# Module_B_High-Speed.net
KiCad netlist of a schematic drawn in Altium Designer
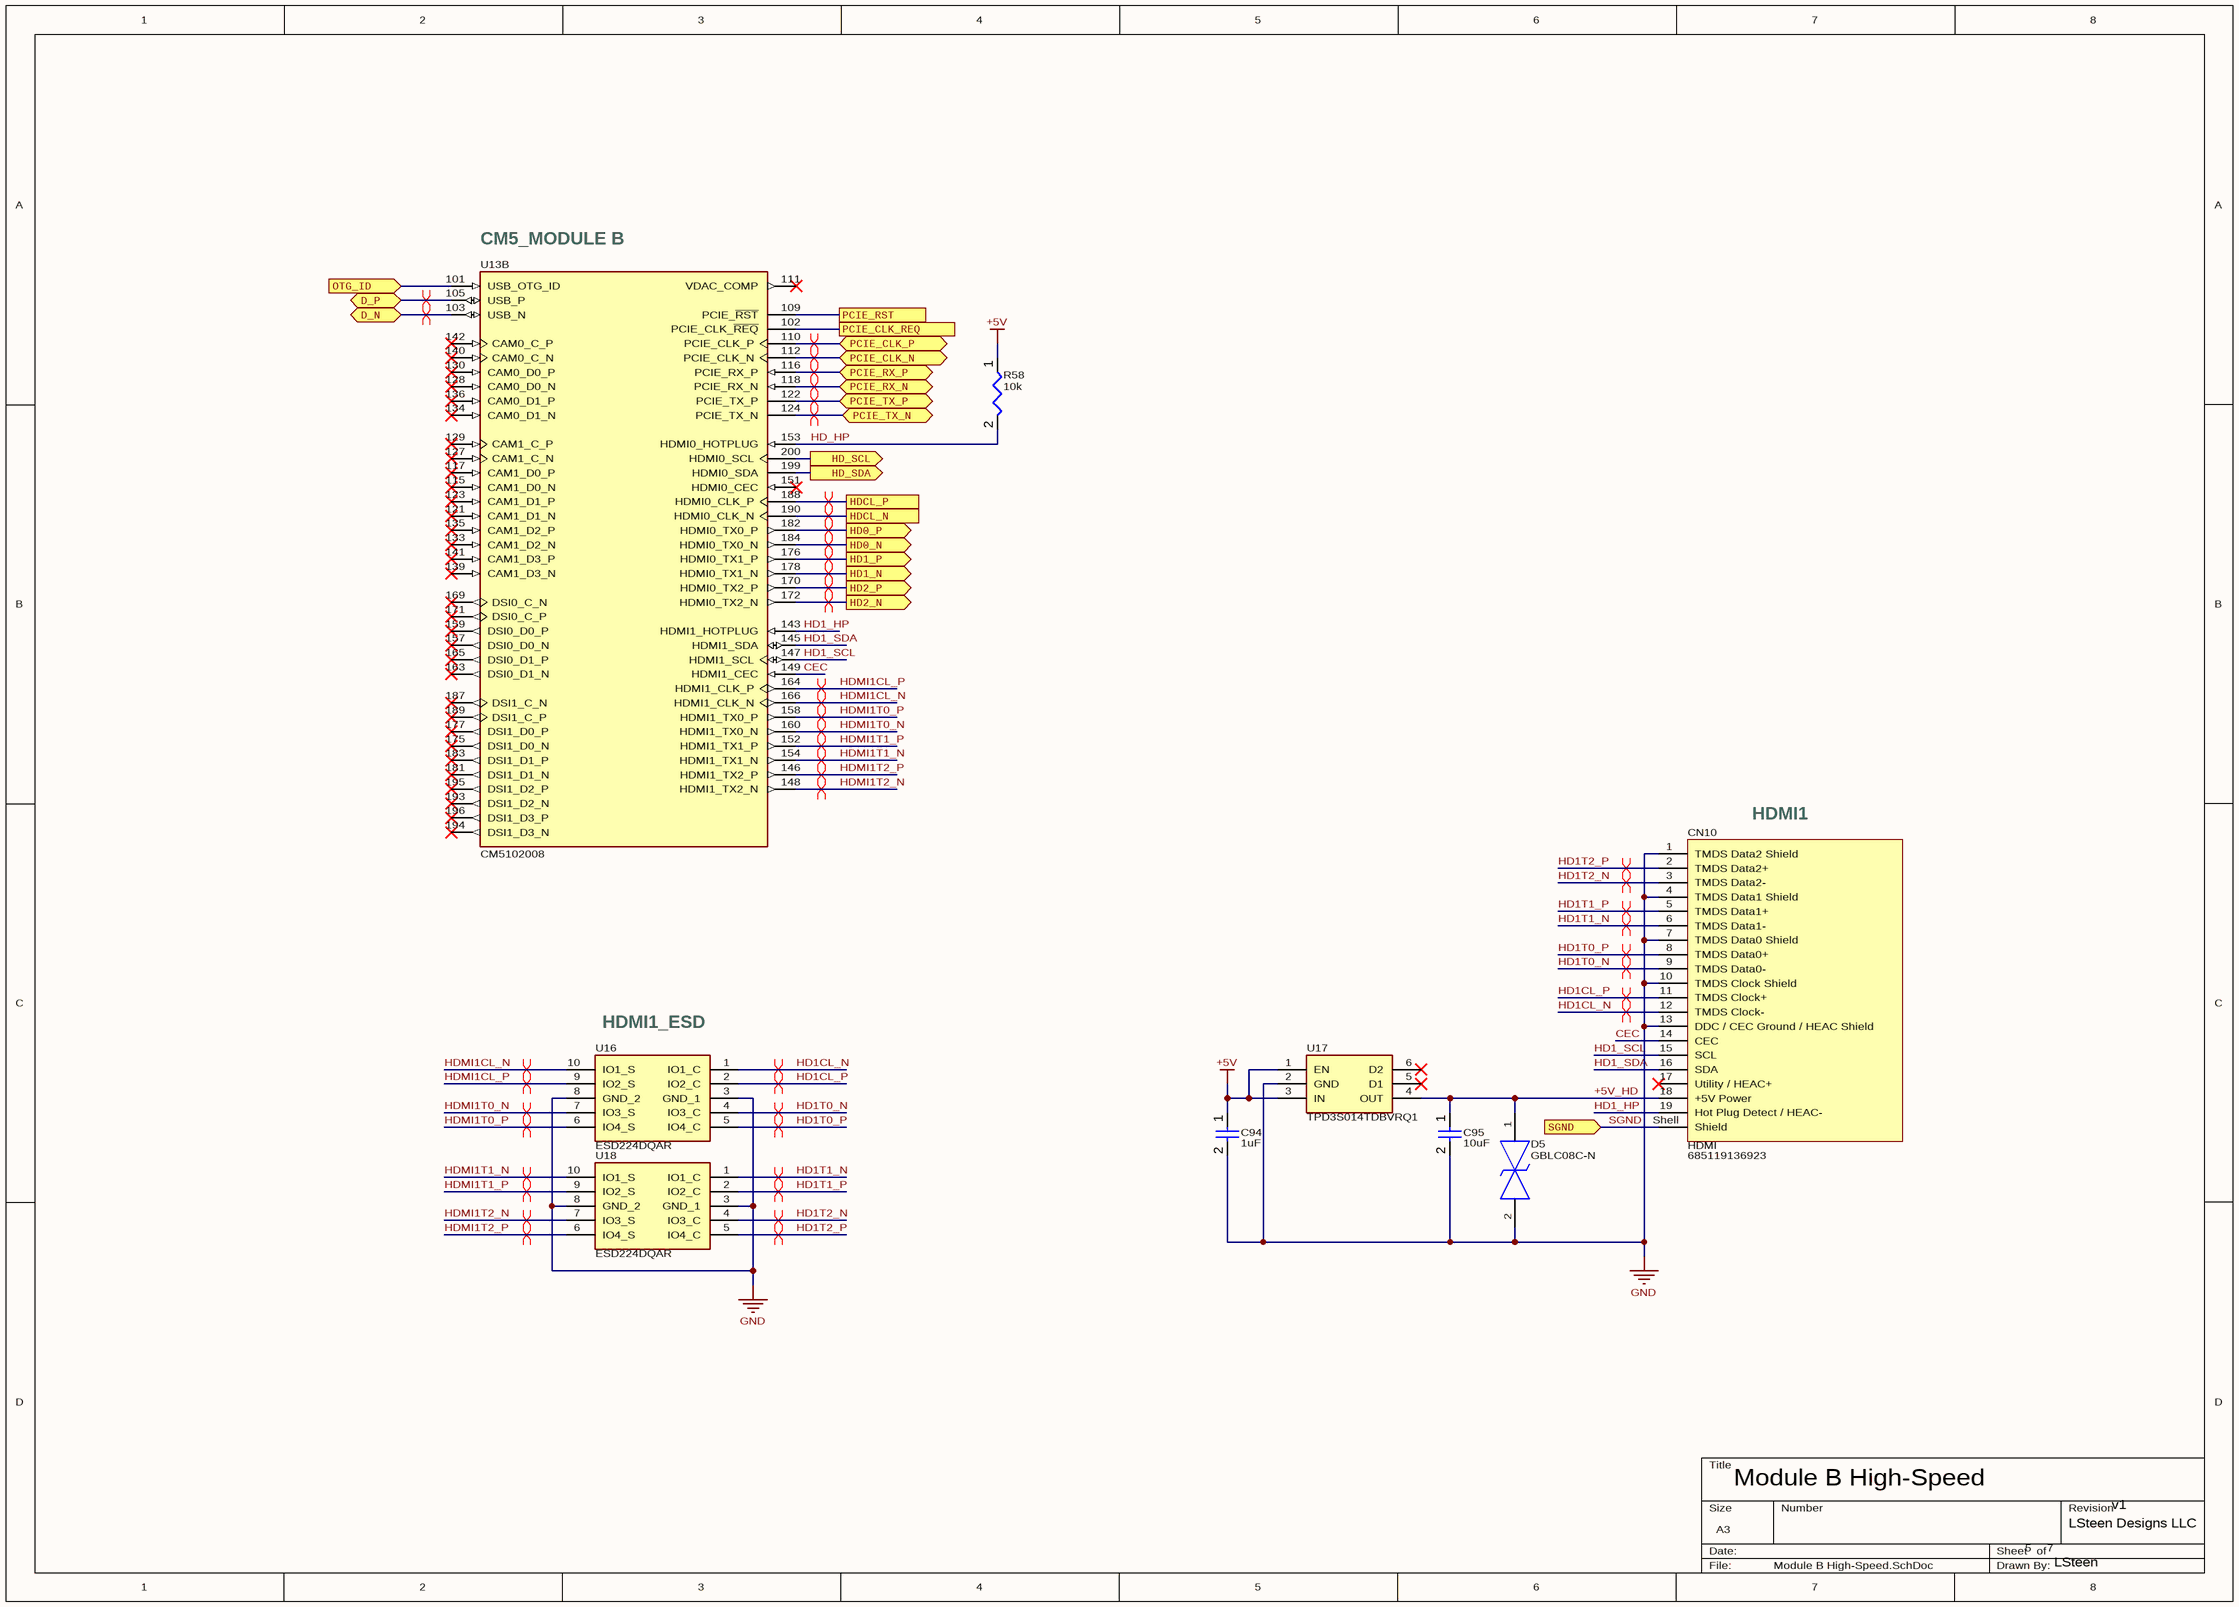
[diagram p0: Module B High-Speed.SchDoc]

(export (version "E")
  (design (tool "Eeschema 10.0.6"))
  (components
    (comp (ref "C94")
      (value "1uF")
      (footprint "CAPC0603(1608)100_L")
      (description "Chip Capacitor, 1uF +/-20%, 10V, 0603, Thickness 1 mm")
      (fields (field (name "TOLERANCE") "10%"))
      (libsource (lib "Colorado Technical University") (part "CAP-NP-2"))
    )
    (comp (ref "C95")
      (value "10uF")
      (footprint "CAPC0805(2012)145_L")
      (description "Chip Capacitor, 10µF +/-20%, 25V, 0805, Thickness 1.45 mm")
      (fields (field (name "TOLERANCE") "10%"))
      (libsource (lib "Colorado Technical University") (part "CAP-NP-2"))
    )
    (comp (ref "CN10")
      (value "HDMI")
      (footprint "685119136923")
      (libsource (lib "Altium Content Vault") (part "HDMI_Type C"))
    )
    (comp (ref "D5")
      (value "GBLC08C-N")
      (footprint "SOD-323_L1.8-W1.3-LS2.5-BI")
      (description "ESD DIODE-BI_LCSC#C314256")
      (libsource (lib "Schlib1") (part "GBLC08C-N"))
    )
    (comp (ref "R58")
      (value "10k")
      (footprint "RESC0402(1005)_L")
      (description "Chip Resistor, 10 kOhms, +/-5 %, 63 mW, -55 to 155 degC, 0402")
      (fields (field (name "TOLERANCE") "5%") (field (name "POWER") "63mW"))
      (libsource (lib "Colorado Technical University") (part "RES-2"))
    )
    (comp (ref "U13")
      (value "CM5102008")
      (footprint "MODULE_CM4102008")
      (description "Raspberry Pi Compute Module 4 with WiFi 2GB RAM 8GB Flash ¦ Raspberry Pi CM4102008")
      (fields (field (name "MF") "Raspberry Pi") (field (name "MP") "CM4102008"))
      (libsource (lib "CM4102008") (part "CM4102008"))
    )
    (comp (ref "U16")
      (value "ESD224DQAR")
      (footprint "SamacSys:ESD224DQAR")
      (description "Integrated Circuit")
      (fields (field (name "MOUSER PART NUMBER") "595-ESD224DQAR"))
      (libsource (lib "SamacSys") (part "ESD224DQAR"))
    )
    (comp (ref "U17")
      (value "TPD3S014TDBVRQ1")
      (footprint "SamacSys:SOT95P280X145-6N")
      (description "Switch")
      (fields (field (name "MOUSER PART NUMBER") "595-TPD3S014TDBVRQ1"))
      (libsource (lib "SamacSys") (part "TPD3S014TDBVRQ1"))
    )
    (comp (ref "U18")
      (value "ESD224DQAR")
      (footprint "SamacSys:ESD224DQAR")
      (description "Integrated Circuit")
      (fields (field (name "MOUSER PART NUMBER") "595-ESD224DQAR"))
      (libsource (lib "SamacSys") (part "ESD224DQAR"))
    )
  )
  (nets
    (net (code "1") (name "+5V") (class "Default")
      (node (ref "C94") (pin "1") (pinfunction "1_1") (pintype "passive"))
      (node (ref "R58") (pin "1") (pinfunction "1_1") (pintype "passive"))
      (node (ref "U17") (pin "1") (pinfunction "EN_1") (pintype "passive"))
      (node (ref "U17") (pin "3") (pinfunction "IN_3") (pintype "passive"))
    )
    (net (code "2") (name "/+5V_HD") (class "Default")
      (node (ref "C95") (pin "1") (pinfunction "1_1") (pintype "passive"))
      (node (ref "CN10") (pin "18") (pinfunction "+5V_Power_18") (pintype "passive"))
      (node (ref "D5") (pin "1") (pinfunction "1_1") (pintype "passive"))
      (node (ref "U17") (pin "4") (pinfunction "OUT_4") (pintype "passive"))
    )
    (net (code "3") (name "/CEC") (class "Default")
      (node (ref "CN10") (pin "14") (pinfunction "CEC_14") (pintype "passive"))
      (node (ref "U13") (pin "149") (pinfunction "HDMI1_CEC_149") (pintype "input"))
    )
    (net (code "4") (name "/D_N") (class "Default")
      (node (ref "U13") (pin "103") (pinfunction "USB_N_103") (pintype "bidirectional"))
    )
    (net (code "5") (name "/D_P") (class "Default")
      (node (ref "U13") (pin "105") (pinfunction "USB_P_105") (pintype "bidirectional"))
    )
    (net (code "6") (name "/HD0_N") (class "Default")
      (node (ref "U13") (pin "184") (pinfunction "HDMI0_TX0_N_184") (pintype "output"))
    )
    (net (code "7") (name "/HD0_P") (class "Default")
      (node (ref "U13") (pin "182") (pinfunction "HDMI0_TX0_P_182") (pintype "output"))
    )
    (net (code "8") (name "/HD1CL_N") (class "Default")
      (node (ref "CN10") (pin "12") (pinfunction "TMDS_Clock-_12") (pintype "passive"))
      (node (ref "U16") (pin "1") (pinfunction "IO1_C_1") (pintype "passive"))
    )
    (net (code "9") (name "/HD1CL_P") (class "Default")
      (node (ref "CN10") (pin "11") (pinfunction "TMDS_Clock+_11") (pintype "passive"))
      (node (ref "U16") (pin "2") (pinfunction "IO2_C_2") (pintype "passive"))
    )
    (net (code "10") (name "/HD1T0_N") (class "Default")
      (node (ref "CN10") (pin "9") (pinfunction "TMDS_Data0-_9") (pintype "passive"))
      (node (ref "U16") (pin "4") (pinfunction "IO3_C_4") (pintype "passive"))
    )
    (net (code "11") (name "/HD1T0_P") (class "Default")
      (node (ref "CN10") (pin "8") (pinfunction "TMDS_Data0+_8") (pintype "passive"))
      (node (ref "U16") (pin "5") (pinfunction "IO4_C_5") (pintype "passive"))
    )
    (net (code "12") (name "/HD1T1_N") (class "Default")
      (node (ref "CN10") (pin "6") (pinfunction "TMDS_Data1-_6") (pintype "passive"))
      (node (ref "U18") (pin "1") (pinfunction "IO1_C_1") (pintype "passive"))
    )
    (net (code "13") (name "/HD1T1_P") (class "Default")
      (node (ref "CN10") (pin "5") (pinfunction "TMDS_Data1+_5") (pintype "passive"))
      (node (ref "U18") (pin "2") (pinfunction "IO2_C_2") (pintype "passive"))
    )
    (net (code "14") (name "/HD1T2_N") (class "Default")
      (node (ref "CN10") (pin "3") (pinfunction "TMDS_Data2-_3") (pintype "passive"))
      (node (ref "U18") (pin "4") (pinfunction "IO3_C_4") (pintype "passive"))
    )
    (net (code "15") (name "/HD1T2_P") (class "Default")
      (node (ref "CN10") (pin "2") (pinfunction "TMDS_Data2+_2") (pintype "passive"))
      (node (ref "U18") (pin "5") (pinfunction "IO4_C_5") (pintype "passive"))
    )
    (net (code "16") (name "/HD1_HP") (class "Default")
      (node (ref "CN10") (pin "19") (pinfunction "Hot_Plug_Detect_/_HEAC-_19") (pintype "passive"))
      (node (ref "U13") (pin "143") (pinfunction "HDMI1_HOTPLUG_143") (pintype "input"))
    )
    (net (code "17") (name "/HD1_N") (class "Default")
      (node (ref "U13") (pin "178") (pinfunction "HDMI0_TX1_N_178") (pintype "output"))
    )
    (net (code "18") (name "/HD1_P") (class "Default")
      (node (ref "U13") (pin "176") (pinfunction "HDMI0_TX1_P_176") (pintype "output"))
    )
    (net (code "19") (name "/HD1_SCL") (class "Default")
      (node (ref "CN10") (pin "15") (pinfunction "SCL_15") (pintype "passive"))
      (node (ref "U13") (pin "147") (pinfunction "HDMI1_SCL_147") (pintype "bidirectional"))
    )
    (net (code "20") (name "/HD1_SDA") (class "Default")
      (node (ref "CN10") (pin "16") (pinfunction "SDA_16") (pintype "passive"))
      (node (ref "U13") (pin "145") (pinfunction "HDMI1_SDA_145") (pintype "bidirectional"))
    )
    (net (code "21") (name "/HD2_N") (class "Default")
      (node (ref "U13") (pin "172") (pinfunction "HDMI0_TX2_N_172") (pintype "output"))
    )
    (net (code "22") (name "/HD2_P") (class "Default")
      (node (ref "U13") (pin "170") (pinfunction "HDMI0_TX2_P_170") (pintype "output"))
    )
    (net (code "23") (name "/HDCL_N") (class "Default")
      (node (ref "U13") (pin "190") (pinfunction "HDMI0_CLK_N_190") (pintype "passive"))
    )
    (net (code "24") (name "/HDCL_P") (class "Default")
      (node (ref "U13") (pin "188") (pinfunction "HDMI0_CLK_P_188") (pintype "passive"))
    )
    (net (code "25") (name "/HDMI1CL_N") (class "Default")
      (node (ref "U13") (pin "166") (pinfunction "HDMI1_CLK_N_166") (pintype "output"))
      (node (ref "U16") (pin "10") (pinfunction "IO1_S_10") (pintype "passive"))
    )
    (net (code "26") (name "/HDMI1CL_P") (class "Default")
      (node (ref "U13") (pin "164") (pinfunction "HDMI1_CLK_P_164") (pintype "output"))
      (node (ref "U16") (pin "9") (pinfunction "IO2_S_9") (pintype "passive"))
    )
    (net (code "27") (name "/HDMI1T0_N") (class "Default")
      (node (ref "U13") (pin "160") (pinfunction "HDMI1_TX0_N_160") (pintype "output"))
      (node (ref "U16") (pin "7") (pinfunction "IO3_S_7") (pintype "passive"))
    )
    (net (code "28") (name "/HDMI1T0_P") (class "Default")
      (node (ref "U13") (pin "158") (pinfunction "HDMI1_TX0_P_158") (pintype "output"))
      (node (ref "U16") (pin "6") (pinfunction "IO4_S_6") (pintype "passive"))
    )
    (net (code "29") (name "/HDMI1T1_N") (class "Default")
      (node (ref "U13") (pin "154") (pinfunction "HDMI1_TX1_N_154") (pintype "output"))
      (node (ref "U18") (pin "10") (pinfunction "IO1_S_10") (pintype "passive"))
    )
    (net (code "30") (name "/HDMI1T1_P") (class "Default")
      (node (ref "U13") (pin "152") (pinfunction "HDMI1_TX1_P_152") (pintype "output"))
      (node (ref "U18") (pin "9") (pinfunction "IO2_S_9") (pintype "passive"))
    )
    (net (code "31") (name "/HDMI1T2_N") (class "Default")
      (node (ref "U13") (pin "148") (pinfunction "HDMI1_TX2_N_148") (pintype "output"))
      (node (ref "U18") (pin "7") (pinfunction "IO3_S_7") (pintype "passive"))
    )
    (net (code "32") (name "/HDMI1T2_P") (class "Default")
      (node (ref "U13") (pin "146") (pinfunction "HDMI1_TX2_P_146") (pintype "output"))
      (node (ref "U18") (pin "6") (pinfunction "IO4_S_6") (pintype "passive"))
    )
    (net (code "33") (name "/HD_HP") (class "Default")
      (node (ref "R58") (pin "2") (pinfunction "2_2") (pintype "passive"))
      (node (ref "U13") (pin "153") (pinfunction "HDMI0_HOTPLUG_153") (pintype "input"))
    )
    (net (code "34") (name "/HD_SCL") (class "Default")
      (node (ref "U13") (pin "200") (pinfunction "HDMI0_SCL_200") (pintype "passive"))
    )
    (net (code "35") (name "/HD_SDA") (class "Default")
      (node (ref "U13") (pin "199") (pinfunction "HDMI0_SDA_199") (pintype "passive"))
    )
    (net (code "36") (name "/OTG_ID") (class "Default")
      (node (ref "U13") (pin "101") (pinfunction "USB_OTG_ID_101") (pintype "input"))
    )
    (net (code "37") (name "/PCIE_CLK_N") (class "Default")
      (node (ref "U13") (pin "112") (pinfunction "PCIE_CLK_N_112") (pintype "passive"))
    )
    (net (code "38") (name "/PCIE_CLK_P") (class "Default")
      (node (ref "U13") (pin "110") (pinfunction "PCIE_CLK_P_110") (pintype "passive"))
    )
    (net (code "39") (name "/PCIE_CLK_REQ") (class "Default")
      (node (ref "U13") (pin "102") (pinfunction "PCIE_CLK_~{REQ}_102") (pintype "passive"))
    )
    (net (code "40") (name "/PCIE_RST") (class "Default")
      (node (ref "U13") (pin "109") (pinfunction "PCIE_~{RST}_109") (pintype "passive"))
    )
    (net (code "41") (name "/PCIE_RX_N") (class "Default")
      (node (ref "U13") (pin "118") (pinfunction "PCIE_RX_N_118") (pintype "input"))
    )
    (net (code "42") (name "/PCIE_RX_P") (class "Default")
      (node (ref "U13") (pin "116") (pinfunction "PCIE_RX_P_116") (pintype "input"))
    )
    (net (code "43") (name "/PCIE_TX_N") (class "Default")
      (node (ref "U13") (pin "124") (pinfunction "PCIE_TX_N_124") (pintype "passive"))
    )
    (net (code "44") (name "/PCIE_TX_P") (class "Default")
      (node (ref "U13") (pin "122") (pinfunction "PCIE_TX_P_122") (pintype "passive"))
    )
    (net (code "45") (name "/SGND") (class "Default")
      (node (ref "CN10") (pin "Shell") (pinfunction "Shield_Shell") (pintype "passive"))
    )
    (net (code "46") (name "GND") (class "Default")
      (node (ref "C94") (pin "2") (pinfunction "2_2") (pintype "passive"))
      (node (ref "C95") (pin "2") (pinfunction "2_2") (pintype "passive"))
      (node (ref "CN10") (pin "1") (pinfunction "TMDS_Data2_Shield_1") (pintype "passive"))
      (node (ref "CN10") (pin "10") (pinfunction "TMDS_Clock_Shield_10") (pintype "passive"))
      (node (ref "CN10") (pin "13") (pinfunction "DDC_/_CEC_Ground_/_HEAC_Shield_13") (pintype "passive"))
      (node (ref "CN10") (pin "4") (pinfunction "TMDS_Data1_Shield_4") (pintype "passive"))
      (node (ref "CN10") (pin "7") (pinfunction "TMDS_Data0_Shield_7") (pintype "passive"))
      (node (ref "D5") (pin "2") (pinfunction "2_2") (pintype "passive"))
      (node (ref "U16") (pin "3") (pinfunction "GND_1_3") (pintype "passive"))
      (node (ref "U16") (pin "8") (pinfunction "GND_2_8") (pintype "passive"))
      (node (ref "U17") (pin "2") (pinfunction "GND_2") (pintype "passive"))
      (node (ref "U18") (pin "3") (pinfunction "GND_1_3") (pintype "passive"))
      (node (ref "U18") (pin "8") (pinfunction "GND_2_8") (pintype "passive"))
    )
    (net (code "47") (name "unconnected-(CN10-Utility_{slash}_HEAC+-Pad17)") (class "Default")
      (node (ref "CN10") (pin "17") (pinfunction "Utility_/_HEAC+_17") (pintype "passive+no_connect"))
    )
    (net (code "48") (name "unconnected-(U13B-CAM0_C_N-Pad140)") (class "Default")
      (node (ref "U13") (pin "140") (pinfunction "CAM0_C_N_140") (pintype "input+no_connect"))
    )
    (net (code "49") (name "unconnected-(U13B-CAM0_C_P-Pad142)") (class "Default")
      (node (ref "U13") (pin "142") (pinfunction "CAM0_C_P_142") (pintype "input+no_connect"))
    )
    (net (code "50") (name "unconnected-(U13B-CAM0_D0_N-Pad128)") (class "Default")
      (node (ref "U13") (pin "128") (pinfunction "CAM0_D0_N_128") (pintype "input+no_connect"))
    )
    (net (code "51") (name "unconnected-(U13B-CAM0_D0_P-Pad130)") (class "Default")
      (node (ref "U13") (pin "130") (pinfunction "CAM0_D0_P_130") (pintype "input+no_connect"))
    )
    (net (code "52") (name "unconnected-(U13B-CAM0_D1_N-Pad134)") (class "Default")
      (node (ref "U13") (pin "134") (pinfunction "CAM0_D1_N_134") (pintype "input+no_connect"))
    )
    (net (code "53") (name "unconnected-(U13B-CAM0_D1_P-Pad136)") (class "Default")
      (node (ref "U13") (pin "136") (pinfunction "CAM0_D1_P_136") (pintype "input+no_connect"))
    )
    (net (code "54") (name "unconnected-(U13B-CAM1_C_N-Pad127)") (class "Default")
      (node (ref "U13") (pin "127") (pinfunction "CAM1_C_N_127") (pintype "input+no_connect"))
    )
    (net (code "55") (name "unconnected-(U13B-CAM1_C_P-Pad129)") (class "Default")
      (node (ref "U13") (pin "129") (pinfunction "CAM1_C_P_129") (pintype "input+no_connect"))
    )
    (net (code "56") (name "unconnected-(U13B-CAM1_D0_N-Pad115)") (class "Default")
      (node (ref "U13") (pin "115") (pinfunction "CAM1_D0_N_115") (pintype "input+no_connect"))
    )
    (net (code "57") (name "unconnected-(U13B-CAM1_D0_P-Pad117)") (class "Default")
      (node (ref "U13") (pin "117") (pinfunction "CAM1_D0_P_117") (pintype "input+no_connect"))
    )
    (net (code "58") (name "unconnected-(U13B-CAM1_D1_N-Pad121)") (class "Default")
      (node (ref "U13") (pin "121") (pinfunction "CAM1_D1_N_121") (pintype "input+no_connect"))
    )
    (net (code "59") (name "unconnected-(U13B-CAM1_D1_P-Pad123)") (class "Default")
      (node (ref "U13") (pin "123") (pinfunction "CAM1_D1_P_123") (pintype "input+no_connect"))
    )
    (net (code "60") (name "unconnected-(U13B-CAM1_D2_N-Pad133)") (class "Default")
      (node (ref "U13") (pin "133") (pinfunction "CAM1_D2_N_133") (pintype "input+no_connect"))
    )
    (net (code "61") (name "unconnected-(U13B-CAM1_D2_P-Pad135)") (class "Default")
      (node (ref "U13") (pin "135") (pinfunction "CAM1_D2_P_135") (pintype "input+no_connect"))
    )
    (net (code "62") (name "unconnected-(U13B-CAM1_D3_N-Pad139)") (class "Default")
      (node (ref "U13") (pin "139") (pinfunction "CAM1_D3_N_139") (pintype "input+no_connect"))
    )
    (net (code "63") (name "unconnected-(U13B-CAM1_D3_P-Pad141)") (class "Default")
      (node (ref "U13") (pin "141") (pinfunction "CAM1_D3_P_141") (pintype "input+no_connect"))
    )
    (net (code "64") (name "unconnected-(U13B-DSI0_C_N-Pad169)") (class "Default")
      (node (ref "U13") (pin "169") (pinfunction "DSI0_C_N_169") (pintype "output+no_connect"))
    )
    (net (code "65") (name "unconnected-(U13B-DSI0_C_P-Pad171)") (class "Default")
      (node (ref "U13") (pin "171") (pinfunction "DSI0_C_P_171") (pintype "output+no_connect"))
    )
    (net (code "66") (name "unconnected-(U13B-DSI0_D0_N-Pad157)") (class "Default")
      (node (ref "U13") (pin "157") (pinfunction "DSI0_D0_N_157") (pintype "output+no_connect"))
    )
    (net (code "67") (name "unconnected-(U13B-DSI0_D0_P-Pad159)") (class "Default")
      (node (ref "U13") (pin "159") (pinfunction "DSI0_D0_P_159") (pintype "output+no_connect"))
    )
    (net (code "68") (name "unconnected-(U13B-DSI0_D1_N-Pad163)") (class "Default")
      (node (ref "U13") (pin "163") (pinfunction "DSI0_D1_N_163") (pintype "output+no_connect"))
    )
    (net (code "69") (name "unconnected-(U13B-DSI0_D1_P-Pad165)") (class "Default")
      (node (ref "U13") (pin "165") (pinfunction "DSI0_D1_P_165") (pintype "output+no_connect"))
    )
    (net (code "70") (name "unconnected-(U13B-DSI1_C_N-Pad187)") (class "Default")
      (node (ref "U13") (pin "187") (pinfunction "DSI1_C_N_187") (pintype "output+no_connect"))
    )
    (net (code "71") (name "unconnected-(U13B-DSI1_C_P-Pad189)") (class "Default")
      (node (ref "U13") (pin "189") (pinfunction "DSI1_C_P_189") (pintype "output+no_connect"))
    )
    (net (code "72") (name "unconnected-(U13B-DSI1_D0_N-Pad175)") (class "Default")
      (node (ref "U13") (pin "175") (pinfunction "DSI1_D0_N_175") (pintype "output+no_connect"))
    )
    (net (code "73") (name "unconnected-(U13B-DSI1_D0_P-Pad177)") (class "Default")
      (node (ref "U13") (pin "177") (pinfunction "DSI1_D0_P_177") (pintype "output+no_connect"))
    )
    (net (code "74") (name "unconnected-(U13B-DSI1_D1_N-Pad181)") (class "Default")
      (node (ref "U13") (pin "181") (pinfunction "DSI1_D1_N_181") (pintype "output+no_connect"))
    )
    (net (code "75") (name "unconnected-(U13B-DSI1_D1_P-Pad183)") (class "Default")
      (node (ref "U13") (pin "183") (pinfunction "DSI1_D1_P_183") (pintype "output+no_connect"))
    )
    (net (code "76") (name "unconnected-(U13B-DSI1_D2_N-Pad193)") (class "Default")
      (node (ref "U13") (pin "193") (pinfunction "DSI1_D2_N_193") (pintype "output+no_connect"))
    )
    (net (code "77") (name "unconnected-(U13B-DSI1_D2_P-Pad195)") (class "Default")
      (node (ref "U13") (pin "195") (pinfunction "DSI1_D2_P_195") (pintype "output+no_connect"))
    )
    (net (code "78") (name "unconnected-(U13B-DSI1_D3_N-Pad194)") (class "Default")
      (node (ref "U13") (pin "194") (pinfunction "DSI1_D3_N_194") (pintype "output+no_connect"))
    )
    (net (code "79") (name "unconnected-(U13B-DSI1_D3_P-Pad196)") (class "Default")
      (node (ref "U13") (pin "196") (pinfunction "DSI1_D3_P_196") (pintype "output+no_connect"))
    )
    (net (code "80") (name "unconnected-(U13B-HDMI0_CEC-Pad151)") (class "Default")
      (node (ref "U13") (pin "151") (pinfunction "HDMI0_CEC_151") (pintype "input+no_connect"))
    )
    (net (code "81") (name "unconnected-(U13B-VDAC_COMP-Pad111)") (class "Default")
      (node (ref "U13") (pin "111") (pinfunction "VDAC_COMP_111") (pintype "output+no_connect"))
    )
    (net (code "82") (name "unconnected-(U17-D1-Pad5)") (class "Default")
      (node (ref "U17") (pin "5") (pinfunction "D1_5") (pintype "passive+no_connect"))
    )
    (net (code "83") (name "unconnected-(U17-D2-Pad6)") (class "Default")
      (node (ref "U17") (pin "6") (pinfunction "D2_6") (pintype "passive+no_connect"))
    )
  )
)
